# CONNECTOR.net
KiCad netlist of a schematic drawn in Altium Designer
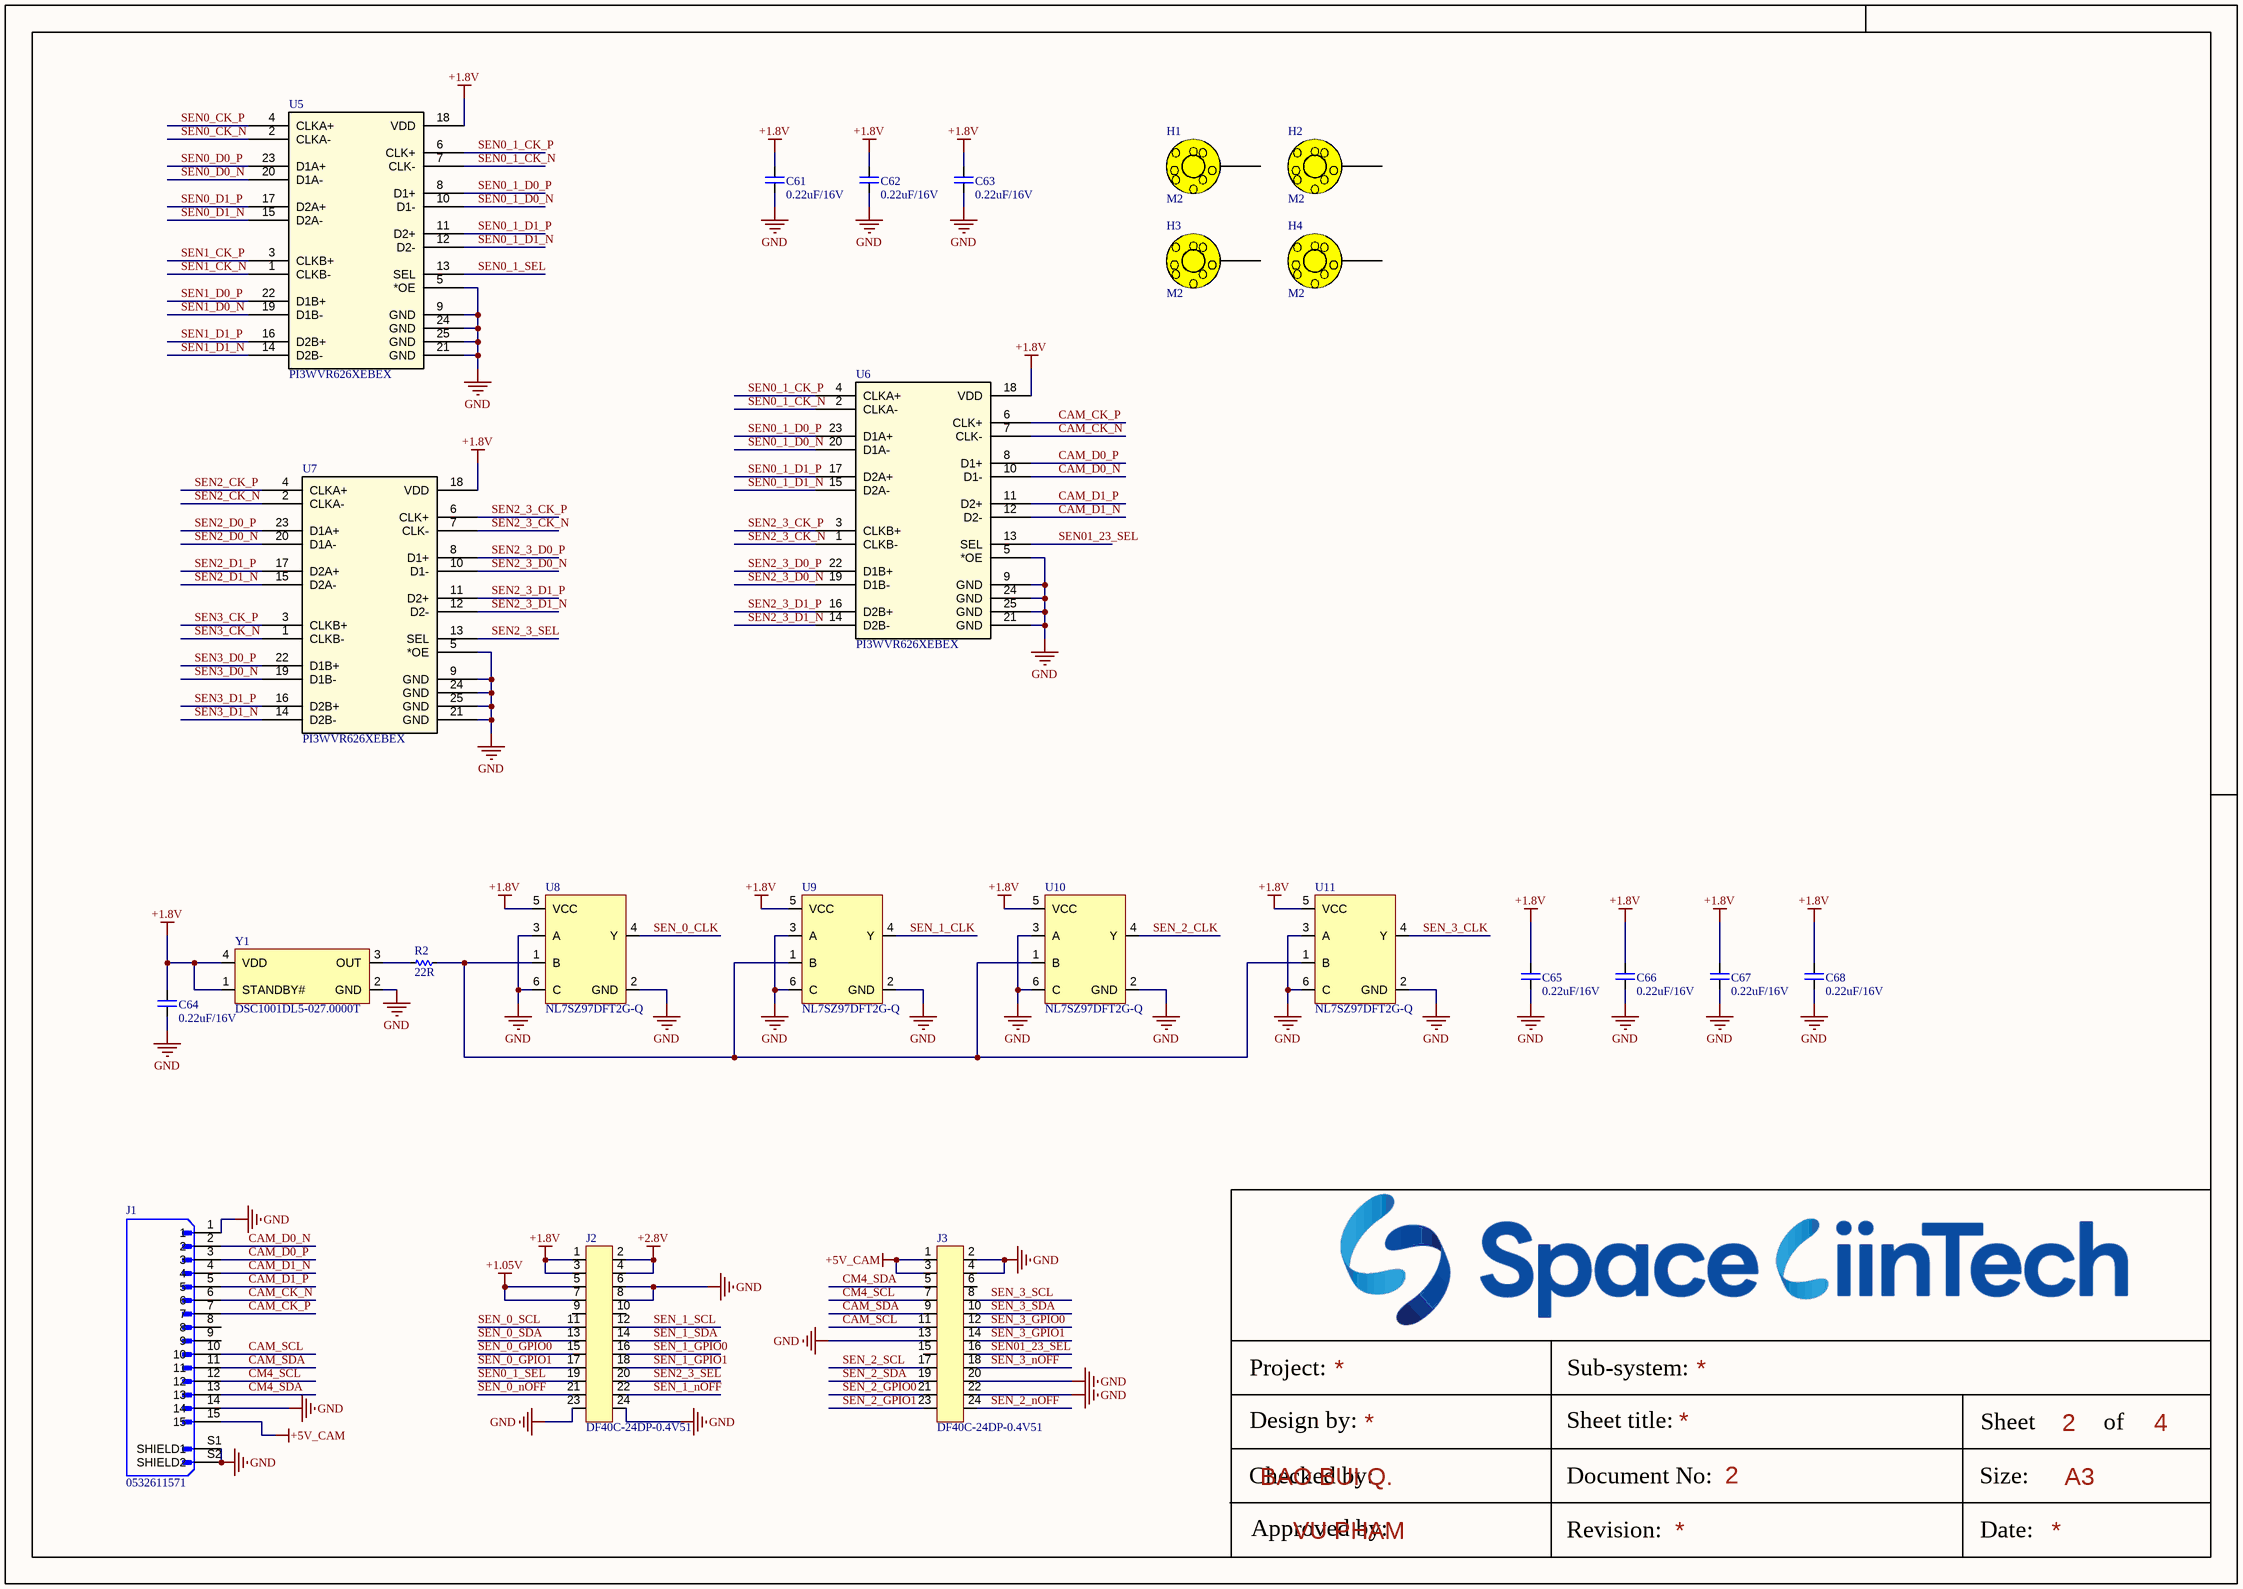
[diagram p0: CONNECTOR.SchDoc]

(export (version "E")
  (design (tool "Eeschema 10.0.6"))
  (components
    (comp (ref "C61")
      (value "0.22uF/16V")
      (footprint "CAP_C_1005X60")
      (description "CAP_Chip")
      (libsource (lib "LABLIB") (part "CAP_SMD"))
    )
    (comp (ref "C62")
      (value "0.22uF/16V")
      (footprint "CAP_C_1005X60")
      (description "CAP_Chip")
      (libsource (lib "LABLIB") (part "CAP_SMD"))
    )
    (comp (ref "C63")
      (value "0.22uF/16V")
      (footprint "CAP_C_1005X60")
      (description "CAP_Chip")
      (libsource (lib "LABLIB") (part "CAP_SMD"))
    )
    (comp (ref "C64")
      (value "0.22uF/16V")
      (footprint "CAP_C_1005X60")
      (description "CAP_Chip")
      (libsource (lib "LABLIB") (part "CAP_SMD"))
    )
    (comp (ref "C65")
      (value "0.22uF/16V")
      (footprint "CAP_C_1005X60")
      (description "CAP_Chip")
      (libsource (lib "LABLIB") (part "CAP_SMD"))
    )
    (comp (ref "C66")
      (value "0.22uF/16V")
      (footprint "CAP_C_1005X60")
      (description "CAP_Chip")
      (libsource (lib "LABLIB") (part "CAP_SMD"))
    )
    (comp (ref "C67")
      (value "0.22uF/16V")
      (footprint "CAP_C_1005X60")
      (description "CAP_Chip")
      (libsource (lib "LABLIB") (part "CAP_SMD"))
    )
    (comp (ref "C68")
      (value "0.22uF/16V")
      (footprint "CAP_C_1005X60")
      (description "CAP_Chip")
      (libsource (lib "LABLIB") (part "CAP_SMD"))
    )
    (comp (ref "H1") (value "M2") (footprint "HEX-2.2mm") (libsource (lib "hex_M3") (part "HEX-M3")))
    (comp (ref "H2") (value "M2") (footprint "HEX-2.2mm") (libsource (lib "hex_M3") (part "HEX-M3")))
    (comp (ref "H3") (value "M2") (footprint "HEX-2.2mm") (libsource (lib "hex_M3") (part "HEX-M3")))
    (comp (ref "H4") (value "M2") (footprint "HEX-2.2mm") (libsource (lib "hex_M3") (part "HEX-M3")))
    (comp (ref "J1")
      (value "0532611571")
      (footprint "0532611571")
      (description "Conn Shrouded Header (4 Sides) HDR 15 POS 1.25mm Solder RA Side Entry SMD PicoBladeâ„¢ T/R")
      (fields (field (name "MP") "532611571") (field (name "MF") "Molex"))
      (libsource (lib "EXP_HW_V2") (part "CONN_SMD_15"))
    )
    (comp (ref "J2")
      (value "DF40C-24DP-0.4V51")
      (footprint "CONN24_6p32X1p85")
      (description "No Description Available")
      (libsource (lib "CAMERA_SchLib") (part "DF40C-24DP-0.4V51"))
    )
    (comp (ref "J3")
      (value "DF40C-24DP-0.4V51")
      (footprint "CONN24_6p32X1p85")
      (description "No Description Available")
      (libsource (lib "CAMERA_SchLib") (part "DF40C-24DP-0.4V51"))
    )
    (comp (ref "R2")
      (value "22R")
      (footprint "RES_C_1005X40")
      (description "RES-Chip")
      (fields
        (field (name "MANUFACTURER") "Generic Components")
        (field (name "PUBLISHER") "Altium Hobart Technology Centre")
      )
      (libsource (lib "LABLIB") (part "RES-SMD"))
    )
    (comp (ref "U5")
      (value "PI3WVR626XEBEX")
      (footprint "PI3WVR626XEBEX_DIO")
      (libsource (lib "CAMERA_SchLib") (part "PI3WVR626XEBEX"))
    )
    (comp (ref "U6")
      (value "PI3WVR626XEBEX")
      (footprint "PI3WVR626XEBEX_DIO")
      (libsource (lib "CAMERA_SchLib") (part "PI3WVR626XEBEX"))
    )
    (comp (ref "U7")
      (value "PI3WVR626XEBEX")
      (footprint "PI3WVR626XEBEX_DIO")
      (libsource (lib "CAMERA_SchLib") (part "PI3WVR626XEBEX"))
    )
    (comp (ref "U8")
      (value "NL7SZ97DFT2G-Q")
      (footprint "SC-88")
      (libsource (lib "CAMERA_SchLib") (part "IC_FLEXLOGIC_NL7SZ97DFT2G-Q"))
    )
    (comp (ref "U9")
      (value "NL7SZ97DFT2G-Q")
      (footprint "SC-88")
      (libsource (lib "CAMERA_SchLib") (part "IC_FLEXLOGIC_NL7SZ97DFT2G-Q"))
    )
    (comp (ref "U10")
      (value "NL7SZ97DFT2G-Q")
      (footprint "SC-88")
      (libsource (lib "CAMERA_SchLib") (part "IC_FLEXLOGIC_NL7SZ97DFT2G-Q"))
    )
    (comp (ref "U11")
      (value "NL7SZ97DFT2G-Q")
      (footprint "SC-88")
      (libsource (lib "CAMERA_SchLib") (part "IC_FLEXLOGIC_NL7SZ97DFT2G-Q"))
    )
    (comp (ref "Y1")
      (value "DSC1001DL5-027.0000T")
      (footprint "OSCDFN250X200X89-4N")
      (libsource (lib "CAMERA_SchLib") (part "Y_OSC27MHz_DSC1001DL5-027.0000T"))
    )
  )
  (nets
    (net (code "1") (name "+1.05V") (class "Default")
      (node (ref "J2") (pin "5") (pintype "passive"))
      (node (ref "J2") (pin "7") (pintype "passive"))
    )
    (net (code "2") (name "+1.8V") (class "Default")
      (node (ref "C61") (pin "2") (pinfunction "2_2") (pintype "passive"))
      (node (ref "C62") (pin "2") (pinfunction "2_2") (pintype "passive"))
      (node (ref "C63") (pin "2") (pinfunction "2_2") (pintype "passive"))
      (node (ref "C64") (pin "2") (pinfunction "2_2") (pintype "passive"))
      (node (ref "C65") (pin "2") (pinfunction "2_2") (pintype "passive"))
      (node (ref "C66") (pin "2") (pinfunction "2_2") (pintype "passive"))
      (node (ref "C67") (pin "2") (pinfunction "2_2") (pintype "passive"))
      (node (ref "C68") (pin "2") (pinfunction "2_2") (pintype "passive"))
      (node (ref "J2") (pin "1") (pintype "passive"))
      (node (ref "J2") (pin "3") (pintype "passive"))
      (node (ref "U10") (pin "5") (pinfunction "VCC_5") (pintype "passive"))
      (node (ref "U11") (pin "5") (pinfunction "VCC_5") (pintype "passive"))
      (node (ref "U5") (pin "18") (pinfunction "VDD_18") (pintype "passive"))
      (node (ref "U6") (pin "18") (pinfunction "VDD_18") (pintype "passive"))
      (node (ref "U7") (pin "18") (pinfunction "VDD_18") (pintype "passive"))
      (node (ref "U8") (pin "5") (pinfunction "VCC_5") (pintype "passive"))
      (node (ref "U9") (pin "5") (pinfunction "VCC_5") (pintype "passive"))
      (node (ref "Y1") (pin "1") (pinfunction "STANDBY#_1") (pintype "passive"))
      (node (ref "Y1") (pin "4") (pinfunction "VDD_4") (pintype "passive"))
    )
    (net (code "3") (name "+2.8V") (class "Default")
      (node (ref "J2") (pin "2") (pintype "passive"))
      (node (ref "J2") (pin "4") (pintype "passive"))
    )
    (net (code "4") (name "+5V_CAM") (class "Default")
      (node (ref "J1") (pin "15") (pinfunction "15_15") (pintype "passive"))
      (node (ref "J3") (pin "1") (pintype "passive"))
      (node (ref "J3") (pin "3") (pintype "passive"))
    )
    (net (code "5") (name "/CAM_CK_N") (class "Default")
      (node (ref "J1") (pin "6") (pinfunction "6_6") (pintype "passive"))
      (node (ref "U6") (pin "7") (pinfunction "CLK-_7") (pintype "passive"))
    )
    (net (code "6") (name "/CAM_CK_P") (class "Default")
      (node (ref "J1") (pin "7") (pinfunction "7_7") (pintype "passive"))
      (node (ref "U6") (pin "6") (pinfunction "CLK+_6") (pintype "passive"))
    )
    (net (code "7") (name "/CAM_D0_N") (class "Default")
      (node (ref "J1") (pin "2") (pinfunction "2_2") (pintype "passive"))
      (node (ref "U6") (pin "10") (pinfunction "D1-_10") (pintype "passive"))
    )
    (net (code "8") (name "/CAM_D0_P") (class "Default")
      (node (ref "J1") (pin "3") (pinfunction "3_3") (pintype "passive"))
      (node (ref "U6") (pin "8") (pinfunction "D1+_8") (pintype "passive"))
    )
    (net (code "9") (name "/CAM_D1_N") (class "Default")
      (node (ref "J1") (pin "4") (pinfunction "4_4") (pintype "passive"))
      (node (ref "U6") (pin "12") (pinfunction "D2-_12") (pintype "passive"))
    )
    (net (code "10") (name "/CAM_D1_P") (class "Default")
      (node (ref "J1") (pin "5") (pinfunction "5_5") (pintype "passive"))
      (node (ref "U6") (pin "11") (pinfunction "D2+_11") (pintype "passive"))
    )
    (net (code "11") (name "/CAM_SCL") (class "Default")
      (node (ref "J1") (pin "10") (pinfunction "10_10") (pintype "passive"))
      (node (ref "J3") (pin "11") (pintype "passive"))
    )
    (net (code "12") (name "/CAM_SDA") (class "Default")
      (node (ref "J1") (pin "11") (pinfunction "11_11") (pintype "passive"))
      (node (ref "J3") (pin "9") (pintype "passive"))
    )
    (net (code "13") (name "/CM4_SCL") (class "Default")
      (node (ref "J1") (pin "12") (pinfunction "12_12") (pintype "passive"))
      (node (ref "J3") (pin "7") (pintype "passive"))
    )
    (net (code "14") (name "/CM4_SDA") (class "Default")
      (node (ref "J1") (pin "13") (pinfunction "13_13") (pintype "passive"))
      (node (ref "J3") (pin "5") (pintype "passive"))
    )
    (net (code "15") (name "/SEN0_1_CK_N") (class "Default")
      (node (ref "U5") (pin "7") (pinfunction "CLK-_7") (pintype "passive"))
      (node (ref "U6") (pin "2") (pinfunction "CLKA-_2") (pintype "passive"))
    )
    (net (code "16") (name "/SEN0_1_CK_P") (class "Default")
      (node (ref "U5") (pin "6") (pinfunction "CLK+_6") (pintype "passive"))
      (node (ref "U6") (pin "4") (pinfunction "CLKA+_4") (pintype "passive"))
    )
    (net (code "17") (name "/SEN0_1_D0_N") (class "Default")
      (node (ref "U5") (pin "10") (pinfunction "D1-_10") (pintype "passive"))
      (node (ref "U6") (pin "20") (pinfunction "D1A-_20") (pintype "passive"))
    )
    (net (code "18") (name "/SEN0_1_D0_P") (class "Default")
      (node (ref "U5") (pin "8") (pinfunction "D1+_8") (pintype "passive"))
      (node (ref "U6") (pin "23") (pinfunction "D1A+_23") (pintype "passive"))
    )
    (net (code "19") (name "/SEN0_1_D1_N") (class "Default")
      (node (ref "U5") (pin "12") (pinfunction "D2-_12") (pintype "passive"))
      (node (ref "U6") (pin "15") (pinfunction "D2A-_15") (pintype "passive"))
    )
    (net (code "20") (name "/SEN0_1_D1_P") (class "Default")
      (node (ref "U5") (pin "11") (pinfunction "D2+_11") (pintype "passive"))
      (node (ref "U6") (pin "17") (pinfunction "D2A+_17") (pintype "passive"))
    )
    (net (code "21") (name "/SEN0_1_SEL") (class "Default")
      (node (ref "J2") (pin "19") (pintype "passive"))
      (node (ref "U5") (pin "13") (pinfunction "SEL_13") (pintype "passive"))
    )
    (net (code "22") (name "/SEN0_CK_N") (class "Default")
      (node (ref "U5") (pin "2") (pinfunction "CLKA-_2") (pintype "passive"))
    )
    (net (code "23") (name "/SEN0_CK_P") (class "Default")
      (node (ref "U5") (pin "4") (pinfunction "CLKA+_4") (pintype "passive"))
    )
    (net (code "24") (name "/SEN0_D0_N") (class "Default")
      (node (ref "U5") (pin "20") (pinfunction "D1A-_20") (pintype "passive"))
    )
    (net (code "25") (name "/SEN0_D0_P") (class "Default")
      (node (ref "U5") (pin "23") (pinfunction "D1A+_23") (pintype "passive"))
    )
    (net (code "26") (name "/SEN0_D1_N") (class "Default")
      (node (ref "U5") (pin "15") (pinfunction "D2A-_15") (pintype "passive"))
    )
    (net (code "27") (name "/SEN0_D1_P") (class "Default")
      (node (ref "U5") (pin "17") (pinfunction "D2A+_17") (pintype "passive"))
    )
    (net (code "28") (name "/SEN01_23_SEL") (class "Default")
      (node (ref "J3") (pin "16") (pintype "passive"))
      (node (ref "U6") (pin "13") (pinfunction "SEL_13") (pintype "passive"))
    )
    (net (code "29") (name "/SEN1_CK_N") (class "Default")
      (node (ref "U5") (pin "1") (pinfunction "CLKB-_1") (pintype "passive"))
    )
    (net (code "30") (name "/SEN1_CK_P") (class "Default")
      (node (ref "U5") (pin "3") (pinfunction "CLKB+_3") (pintype "passive"))
    )
    (net (code "31") (name "/SEN1_D0_N") (class "Default")
      (node (ref "U5") (pin "19") (pinfunction "D1B-_19") (pintype "passive"))
    )
    (net (code "32") (name "/SEN1_D0_P") (class "Default")
      (node (ref "U5") (pin "22") (pinfunction "D1B+_22") (pintype "passive"))
    )
    (net (code "33") (name "/SEN1_D1_N") (class "Default")
      (node (ref "U5") (pin "14") (pinfunction "D2B-_14") (pintype "passive"))
    )
    (net (code "34") (name "/SEN1_D1_P") (class "Default")
      (node (ref "U5") (pin "16") (pinfunction "D2B+_16") (pintype "passive"))
    )
    (net (code "35") (name "/SEN2_3_CK_N") (class "Default")
      (node (ref "U6") (pin "1") (pinfunction "CLKB-_1") (pintype "passive"))
      (node (ref "U7") (pin "7") (pinfunction "CLK-_7") (pintype "passive"))
    )
    (net (code "36") (name "/SEN2_3_CK_P") (class "Default")
      (node (ref "U6") (pin "3") (pinfunction "CLKB+_3") (pintype "passive"))
      (node (ref "U7") (pin "6") (pinfunction "CLK+_6") (pintype "passive"))
    )
    (net (code "37") (name "/SEN2_3_D0_N") (class "Default")
      (node (ref "U6") (pin "19") (pinfunction "D1B-_19") (pintype "passive"))
      (node (ref "U7") (pin "10") (pinfunction "D1-_10") (pintype "passive"))
    )
    (net (code "38") (name "/SEN2_3_D0_P") (class "Default")
      (node (ref "U6") (pin "22") (pinfunction "D1B+_22") (pintype "passive"))
      (node (ref "U7") (pin "8") (pinfunction "D1+_8") (pintype "passive"))
    )
    (net (code "39") (name "/SEN2_3_D1_N") (class "Default")
      (node (ref "U6") (pin "14") (pinfunction "D2B-_14") (pintype "passive"))
      (node (ref "U7") (pin "12") (pinfunction "D2-_12") (pintype "passive"))
    )
    (net (code "40") (name "/SEN2_3_D1_P") (class "Default")
      (node (ref "U6") (pin "16") (pinfunction "D2B+_16") (pintype "passive"))
      (node (ref "U7") (pin "11") (pinfunction "D2+_11") (pintype "passive"))
    )
    (net (code "41") (name "/SEN2_3_SEL") (class "Default")
      (node (ref "J2") (pin "20") (pintype "passive"))
      (node (ref "U7") (pin "13") (pinfunction "SEL_13") (pintype "passive"))
    )
    (net (code "42") (name "/SEN2_CK_N") (class "Default")
      (node (ref "U7") (pin "2") (pinfunction "CLKA-_2") (pintype "passive"))
    )
    (net (code "43") (name "/SEN2_CK_P") (class "Default")
      (node (ref "U7") (pin "4") (pinfunction "CLKA+_4") (pintype "passive"))
    )
    (net (code "44") (name "/SEN2_D0_N") (class "Default")
      (node (ref "U7") (pin "20") (pinfunction "D1A-_20") (pintype "passive"))
    )
    (net (code "45") (name "/SEN2_D0_P") (class "Default")
      (node (ref "U7") (pin "23") (pinfunction "D1A+_23") (pintype "passive"))
    )
    (net (code "46") (name "/SEN2_D1_N") (class "Default")
      (node (ref "U7") (pin "15") (pinfunction "D2A-_15") (pintype "passive"))
    )
    (net (code "47") (name "/SEN2_D1_P") (class "Default")
      (node (ref "U7") (pin "17") (pinfunction "D2A+_17") (pintype "passive"))
    )
    (net (code "48") (name "/SEN3_CK_N") (class "Default")
      (node (ref "U7") (pin "1") (pinfunction "CLKB-_1") (pintype "passive"))
    )
    (net (code "49") (name "/SEN3_CK_P") (class "Default")
      (node (ref "U7") (pin "3") (pinfunction "CLKB+_3") (pintype "passive"))
    )
    (net (code "50") (name "/SEN3_D0_N") (class "Default")
      (node (ref "U7") (pin "19") (pinfunction "D1B-_19") (pintype "passive"))
    )
    (net (code "51") (name "/SEN3_D0_P") (class "Default")
      (node (ref "U7") (pin "22") (pinfunction "D1B+_22") (pintype "passive"))
    )
    (net (code "52") (name "/SEN3_D1_N") (class "Default")
      (node (ref "U7") (pin "14") (pinfunction "D2B-_14") (pintype "passive"))
    )
    (net (code "53") (name "/SEN3_D1_P") (class "Default")
      (node (ref "U7") (pin "16") (pinfunction "D2B+_16") (pintype "passive"))
    )
    (net (code "54") (name "/SEN_0_CLK") (class "Default")
      (node (ref "U8") (pin "4") (pinfunction "Y_4") (pintype "passive"))
    )
    (net (code "55") (name "/SEN_0_GPIO0") (class "Default") (node (ref "J2") (pin "15") (pintype "passive")))
    (net (code "56") (name "/SEN_0_GPIO1") (class "Default") (node (ref "J2") (pin "17") (pintype "passive")))
    (net (code "57") (name "/SEN_0_SCL") (class "Default") (node (ref "J2") (pin "11") (pintype "passive")))
    (net (code "58") (name "/SEN_0_SDA") (class "Default") (node (ref "J2") (pin "13") (pintype "passive")))
    (net (code "59") (name "/SEN_0_nOFF") (class "Default") (node (ref "J2") (pin "21") (pintype "passive")))
    (net (code "60") (name "/SEN_1_CLK") (class "Default")
      (node (ref "U9") (pin "4") (pinfunction "Y_4") (pintype "passive"))
    )
    (net (code "61") (name "/SEN_1_GPIO0") (class "Default") (node (ref "J2") (pin "16") (pintype "passive")))
    (net (code "62") (name "/SEN_1_GPIO1") (class "Default") (node (ref "J2") (pin "18") (pintype "passive")))
    (net (code "63") (name "/SEN_1_SCL") (class "Default") (node (ref "J2") (pin "12") (pintype "passive")))
    (net (code "64") (name "/SEN_1_SDA") (class "Default") (node (ref "J2") (pin "14") (pintype "passive")))
    (net (code "65") (name "/SEN_1_nOFF") (class "Default") (node (ref "J2") (pin "22") (pintype "passive")))
    (net (code "66") (name "/SEN_2_CLK") (class "Default")
      (node (ref "U10") (pin "4") (pinfunction "Y_4") (pintype "passive"))
    )
    (net (code "67") (name "/SEN_2_GPIO0") (class "Default") (node (ref "J3") (pin "21") (pintype "passive")))
    (net (code "68") (name "/SEN_2_GPIO1") (class "Default") (node (ref "J3") (pin "23") (pintype "passive")))
    (net (code "69") (name "/SEN_2_SCL") (class "Default") (node (ref "J3") (pin "17") (pintype "passive")))
    (net (code "70") (name "/SEN_2_SDA") (class "Default") (node (ref "J3") (pin "19") (pintype "passive")))
    (net (code "71") (name "/SEN_2_nOFF") (class "Default") (node (ref "J3") (pin "24") (pintype "passive")))
    (net (code "72") (name "/SEN_3_CLK") (class "Default")
      (node (ref "U11") (pin "4") (pinfunction "Y_4") (pintype "passive"))
    )
    (net (code "73") (name "/SEN_3_GPIO0") (class "Default") (node (ref "J3") (pin "12") (pintype "passive")))
    (net (code "74") (name "/SEN_3_GPIO1") (class "Default") (node (ref "J3") (pin "14") (pintype "passive")))
    (net (code "75") (name "/SEN_3_SCL") (class "Default") (node (ref "J3") (pin "8") (pintype "passive")))
    (net (code "76") (name "/SEN_3_SDA") (class "Default") (node (ref "J3") (pin "10") (pintype "passive")))
    (net (code "77") (name "/SEN_3_nOFF") (class "Default") (node (ref "J3") (pin "18") (pintype "passive")))
    (net (code "78") (name "GND") (class "Default")
      (node (ref "C61") (pin "1") (pinfunction "1_1") (pintype "passive"))
      (node (ref "C62") (pin "1") (pinfunction "1_1") (pintype "passive"))
      (node (ref "C63") (pin "1") (pinfunction "1_1") (pintype "passive"))
      (node (ref "C64") (pin "1") (pinfunction "1_1") (pintype "passive"))
      (node (ref "C65") (pin "1") (pinfunction "1_1") (pintype "passive"))
      (node (ref "C66") (pin "1") (pinfunction "1_1") (pintype "passive"))
      (node (ref "C67") (pin "1") (pinfunction "1_1") (pintype "passive"))
      (node (ref "C68") (pin "1") (pinfunction "1_1") (pintype "passive"))
      (node (ref "J1") (pin "1") (pinfunction "1_1") (pintype "passive"))
      (node (ref "J1") (pin "14") (pinfunction "14_14") (pintype "passive"))
      (node (ref "J1") (pin "S1") (pinfunction "SHIELD1_S1") (pintype "passive"))
      (node (ref "J1") (pin "S2") (pinfunction "SHIELD2_S2") (pintype "passive"))
      (node (ref "J2") (pin "23") (pintype "passive"))
      (node (ref "J2") (pin "24") (pintype "passive"))
      (node (ref "J2") (pin "6") (pintype "passive"))
      (node (ref "J2") (pin "8") (pintype "passive"))
      (node (ref "J3") (pin "13") (pintype "passive"))
      (node (ref "J3") (pin "2") (pintype "passive"))
      (node (ref "J3") (pin "20") (pintype "passive"))
      (node (ref "J3") (pin "22") (pintype "passive"))
      (node (ref "J3") (pin "4") (pintype "passive"))
      (node (ref "U10") (pin "2") (pinfunction "GND_2") (pintype "passive"))
      (node (ref "U10") (pin "3") (pinfunction "A_3") (pintype "passive"))
      (node (ref "U10") (pin "6") (pinfunction "C_6") (pintype "passive"))
      (node (ref "U11") (pin "2") (pinfunction "GND_2") (pintype "passive"))
      (node (ref "U11") (pin "3") (pinfunction "A_3") (pintype "passive"))
      (node (ref "U11") (pin "6") (pinfunction "C_6") (pintype "passive"))
      (node (ref "U5") (pin "21") (pinfunction "GND_21") (pintype "passive"))
      (node (ref "U5") (pin "24") (pinfunction "GND_24") (pintype "passive"))
      (node (ref "U5") (pin "25") (pinfunction "GND_25") (pintype "passive"))
      (node (ref "U5") (pin "5") (pinfunction "*OE_5") (pintype "passive"))
      (node (ref "U5") (pin "9") (pinfunction "GND_9") (pintype "passive"))
      (node (ref "U6") (pin "21") (pinfunction "GND_21") (pintype "passive"))
      (node (ref "U6") (pin "24") (pinfunction "GND_24") (pintype "passive"))
      (node (ref "U6") (pin "25") (pinfunction "GND_25") (pintype "passive"))
      (node (ref "U6") (pin "5") (pinfunction "*OE_5") (pintype "passive"))
      (node (ref "U6") (pin "9") (pinfunction "GND_9") (pintype "passive"))
      (node (ref "U7") (pin "21") (pinfunction "GND_21") (pintype "passive"))
      (node (ref "U7") (pin "24") (pinfunction "GND_24") (pintype "passive"))
      (node (ref "U7") (pin "25") (pinfunction "GND_25") (pintype "passive"))
      (node (ref "U7") (pin "5") (pinfunction "*OE_5") (pintype "passive"))
      (node (ref "U7") (pin "9") (pinfunction "GND_9") (pintype "passive"))
      (node (ref "U8") (pin "2") (pinfunction "GND_2") (pintype "passive"))
      (node (ref "U8") (pin "3") (pinfunction "A_3") (pintype "passive"))
      (node (ref "U8") (pin "6") (pinfunction "C_6") (pintype "passive"))
      (node (ref "U9") (pin "2") (pinfunction "GND_2") (pintype "passive"))
      (node (ref "U9") (pin "3") (pinfunction "A_3") (pintype "passive"))
      (node (ref "U9") (pin "6") (pinfunction "C_6") (pintype "passive"))
      (node (ref "Y1") (pin "2") (pinfunction "GND_2") (pintype "passive"))
    )
    (net (code "79") (name "Net-(U10-B)") (class "Default")
      (node (ref "R2") (pin "1") (pinfunction "1_1") (pintype "passive"))
      (node (ref "U10") (pin "1") (pinfunction "B_1") (pintype "passive"))
      (node (ref "U11") (pin "1") (pinfunction "B_1") (pintype "passive"))
      (node (ref "U8") (pin "1") (pinfunction "B_1") (pintype "passive"))
      (node (ref "U9") (pin "1") (pinfunction "B_1") (pintype "passive"))
    )
    (net (code "80") (name "Net-(Y1-OUT)") (class "Default")
      (node (ref "R2") (pin "2") (pinfunction "2_2") (pintype "passive"))
      (node (ref "Y1") (pin "3") (pinfunction "OUT_3") (pintype "passive"))
    )
    (net (code "81") (name "unconnected-(H1-Pad1)") (class "Default")
      (node (ref "H1") (pin "1") (pinfunction "1_1") (pintype "power_in"))
    )
    (net (code "82") (name "unconnected-(H2-Pad1)") (class "Default")
      (node (ref "H2") (pin "1") (pinfunction "1_1") (pintype "power_in"))
    )
    (net (code "83") (name "unconnected-(H3-Pad1)") (class "Default")
      (node (ref "H3") (pin "1") (pinfunction "1_1") (pintype "power_in"))
    )
    (net (code "84") (name "unconnected-(H4-Pad1)") (class "Default")
      (node (ref "H4") (pin "1") (pinfunction "1_1") (pintype "power_in"))
    )
    (net (code "85") (name "unconnected-(J1-Pad8)") (class "Default")
      (node (ref "J1") (pin "8") (pinfunction "8_8") (pintype "passive"))
    )
    (net (code "86") (name "unconnected-(J1-Pad9)") (class "Default")
      (node (ref "J1") (pin "9") (pinfunction "9_9") (pintype "passive"))
    )
    (net (code "87") (name "unconnected-(J2-Pad9)") (class "Default")
      (node (ref "J2") (pin "9") (pintype "passive"))
    )
    (net (code "88") (name "unconnected-(J2-Pad10)") (class "Default")
      (node (ref "J2") (pin "10") (pintype "passive"))
    )
    (net (code "89") (name "unconnected-(J3-Pad6)") (class "Default")
      (node (ref "J3") (pin "6") (pintype "passive"))
    )
    (net (code "90") (name "unconnected-(J3-Pad15)") (class "Default")
      (node (ref "J3") (pin "15") (pintype "passive"))
    )
  )
)
